# control_board.net
KiCad netlist of a schematic drawn in EAGLE
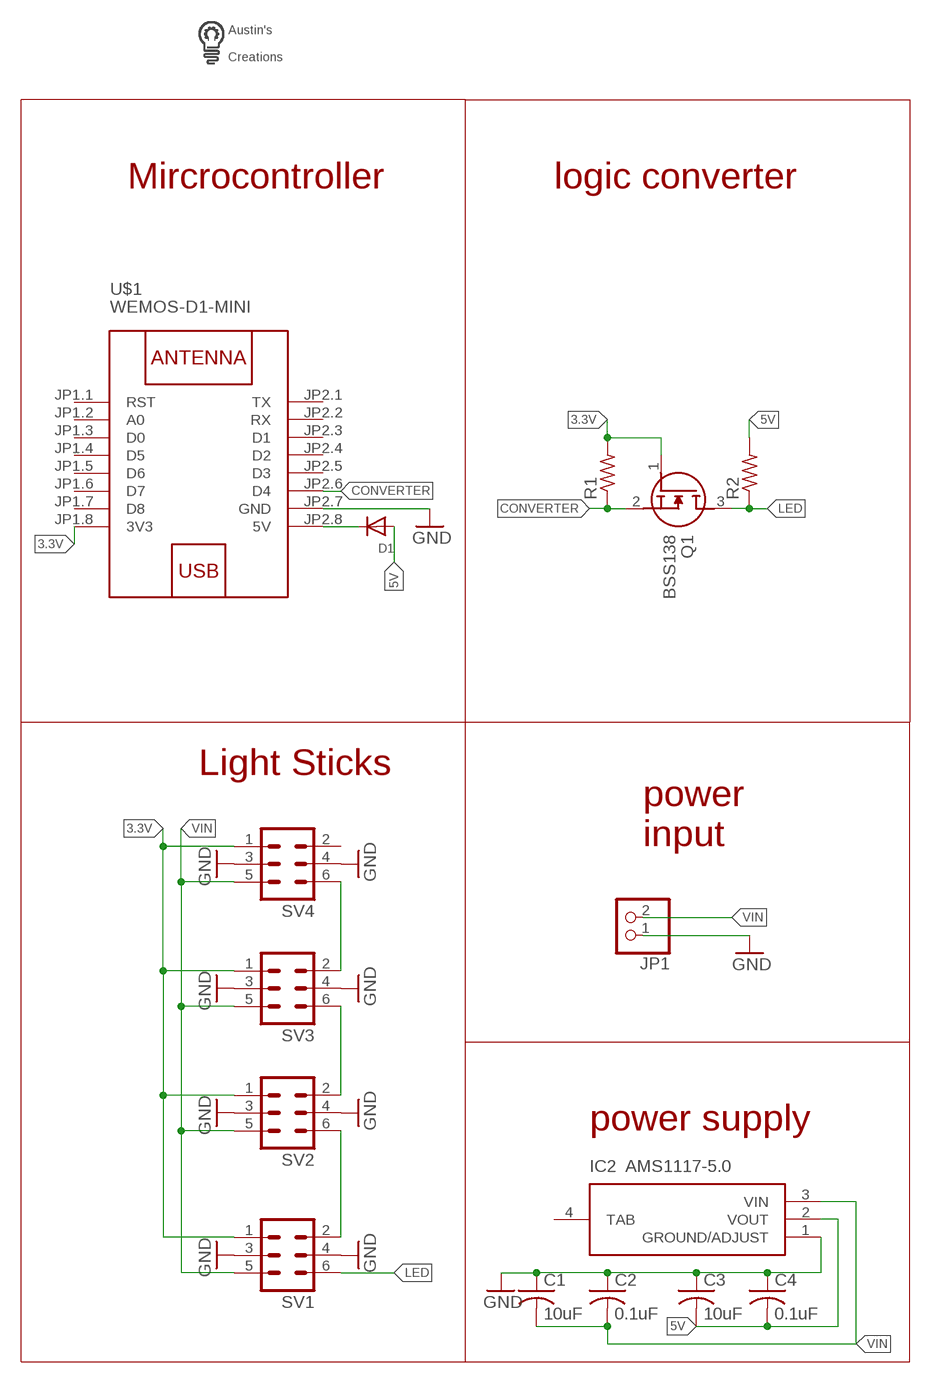
[diagram p0: schematic, sheet 1]

(export (version "E")
  (design (tool "Eeschema 10.0.6"))
  (components
    (comp (ref "C1")
      (value "10uF")
      (footprint "eagle-import:C0603")
      (libsource (lib "eagle-import") (part "C-USC0603"))
    )
    (comp (ref "C2")
      (value "0.1uF")
      (footprint "eagle-import:C0603")
      (libsource (lib "eagle-import") (part "C-USC0603"))
    )
    (comp (ref "C3")
      (value "10uF")
      (footprint "eagle-import:C0603")
      (libsource (lib "eagle-import") (part "C-USC0603"))
    )
    (comp (ref "C4")
      (value "0.1uF")
      (footprint "eagle-import:C0603")
      (libsource (lib "eagle-import") (part "C-USC0603"))
    )
    (comp (ref "D1")
      (value "DIODESOD-123")
      (footprint "eagle-import:SOD-123")
      (libsource (lib "eagle-import") (part "DIODESOD-123"))
    )
    (comp (ref "IC2")
      (value "AMS1117-5.0")
      (footprint "eagle-import:SOT229P700X180-4N")
      (libsource (lib "eagle-import") (part "AMS1117-5.0"))
    )
    (comp (ref "JP1")
      (value "PINHD-1X2")
      (footprint "eagle-import:1X02")
      (libsource (lib "eagle-import") (part "PINHD-1X2"))
    )
    (comp (ref "Q1")
      (value "BSS138")
      (footprint "eagle-import:SOT95P240X120-3N")
      (fields (field (name "MOUSER_PART_NUMBER") "512-BSS138"))
      (libsource (lib "eagle-import") (part "BSS138"))
    )
    (comp (ref "R1")
      (value "R-US_R0603")
      (footprint "eagle-import:R0603")
      (libsource (lib "eagle-import") (part "R-US_R0603"))
    )
    (comp (ref "R2")
      (value "R-US_R0603")
      (footprint "eagle-import:R0603")
      (libsource (lib "eagle-import") (part "R-US_R0603"))
    )
    (comp (ref "SV1")
      (value "MA03-2")
      (footprint "eagle-import:MA03-2")
      (libsource (lib "eagle-import") (part "MA03-2"))
    )
    (comp (ref "SV2")
      (value "MA03-2")
      (footprint "eagle-import:MA03-2")
      (libsource (lib "eagle-import") (part "MA03-2"))
    )
    (comp (ref "SV3")
      (value "MA03-2")
      (footprint "eagle-import:MA03-2")
      (libsource (lib "eagle-import") (part "MA03-2"))
    )
    (comp (ref "SV4")
      (value "MA03-2")
      (footprint "eagle-import:MA03-2")
      (libsource (lib "eagle-import") (part "MA03-2"))
    )
    (comp (ref "U$1")
      (value "WEMOS-D1-MINI")
      (footprint "eagle-import:WEMOS-D1-MINI")
      (libsource (lib "eagle-import") (part "WEMOS-D1-MINI"))
    )
    (comp (ref "U$2")
      (value "LOGO")
      (footprint "eagle-import:LOGO")
      (libsource (lib "eagle-import") (part "LOGO"))
    )
  )
  (nets
    (net (code "1") (name "3.3V") (class "Default")
      (node (ref "Q1") (pin "1") (pinfunction "G_1") (pintype "bidirectional"))
      (node (ref "R1") (pin "2") (pinfunction "2_2") (pintype "passive"))
      (node (ref "SV1") (pin "1") (pinfunction "1_1") (pintype "passive"))
      (node (ref "SV2") (pin "1") (pinfunction "1_1") (pintype "passive"))
      (node (ref "SV3") (pin "1") (pinfunction "1_1") (pintype "passive"))
      (node (ref "SV4") (pin "1") (pinfunction "1_1") (pintype "passive"))
      (node (ref "U$1") (pin "JP1.8") (pinfunction "3V3_JP1.8") (pintype "power_in"))
    )
    (net (code "2") (name "5V") (class "Default")
      (node (ref "C3") (pin "2") (pinfunction "2_2") (pintype "passive"))
      (node (ref "C4") (pin "2") (pinfunction "2_2") (pintype "passive"))
      (node (ref "D1") (pin "A") (pinfunction "A_A") (pintype "passive"))
      (node (ref "IC2") (pin "2") (pinfunction "VOUT_2") (pintype "bidirectional"))
      (node (ref "R2") (pin "2") (pinfunction "2_2") (pintype "passive"))
    )
    (net (code "3") (name "CONVERTER") (class "Default")
      (node (ref "Q1") (pin "2") (pinfunction "S_2") (pintype "bidirectional"))
      (node (ref "R1") (pin "1") (pinfunction "1_1") (pintype "passive"))
      (node (ref "U$1") (pin "JP2.6") (pinfunction "D4_JP2.6") (pintype "bidirectional"))
    )
    (net (code "4") (name "GND") (class "Default")
      (node (ref "C1") (pin "1") (pinfunction "1_1") (pintype "passive"))
      (node (ref "C2") (pin "1") (pinfunction "1_1") (pintype "passive"))
      (node (ref "C3") (pin "1") (pinfunction "1_1") (pintype "passive"))
      (node (ref "C4") (pin "1") (pinfunction "1_1") (pintype "passive"))
      (node (ref "IC2") (pin "1") (pinfunction "GROUND/ADJUST_1") (pintype "bidirectional"))
      (node (ref "JP1") (pin "1") (pinfunction "1_1") (pintype "passive"))
      (node (ref "SV1") (pin "3") (pinfunction "3_3") (pintype "passive"))
      (node (ref "SV1") (pin "4") (pinfunction "4_4") (pintype "passive"))
      (node (ref "SV2") (pin "3") (pinfunction "3_3") (pintype "passive"))
      (node (ref "SV2") (pin "4") (pinfunction "4_4") (pintype "passive"))
      (node (ref "SV3") (pin "3") (pinfunction "3_3") (pintype "passive"))
      (node (ref "SV3") (pin "4") (pinfunction "4_4") (pintype "passive"))
      (node (ref "SV4") (pin "3") (pinfunction "3_3") (pintype "passive"))
      (node (ref "SV4") (pin "4") (pinfunction "4_4") (pintype "passive"))
      (node (ref "U$1") (pin "JP2.7") (pinfunction "GND_JP2.7") (pintype "power_in"))
    )
    (net (code "5") (name "LED") (class "Default")
      (node (ref "Q1") (pin "3") (pinfunction "D_3") (pintype "bidirectional"))
      (node (ref "R2") (pin "1") (pinfunction "1_1") (pintype "passive"))
      (node (ref "SV1") (pin "6") (pinfunction "6_6") (pintype "passive"))
    )
    (net (code "6") (name "Net-(SV1-Pad2)") (class "Default")
      (node (ref "SV1") (pin "2") (pinfunction "2_2") (pintype "passive"))
      (node (ref "SV2") (pin "6") (pinfunction "6_6") (pintype "passive"))
    )
    (net (code "7") (name "Net-(SV2-Pad2)") (class "Default")
      (node (ref "SV2") (pin "2") (pinfunction "2_2") (pintype "passive"))
      (node (ref "SV3") (pin "6") (pinfunction "6_6") (pintype "passive"))
    )
    (net (code "8") (name "Net-(SV3-Pad2)") (class "Default")
      (node (ref "SV3") (pin "2") (pinfunction "2_2") (pintype "passive"))
      (node (ref "SV4") (pin "6") (pinfunction "6_6") (pintype "passive"))
    )
    (net (code "9") (name "Net-(U$1-5V)") (class "Default")
      (node (ref "D1") (pin "C") (pinfunction "C_C") (pintype "passive"))
      (node (ref "U$1") (pin "JP2.8") (pinfunction "5V_JP2.8") (pintype "power_in"))
    )
    (net (code "10") (name "VIN") (class "Default")
      (node (ref "C1") (pin "2") (pinfunction "2_2") (pintype "passive"))
      (node (ref "C2") (pin "2") (pinfunction "2_2") (pintype "passive"))
      (node (ref "IC2") (pin "3") (pinfunction "VIN_3") (pintype "bidirectional"))
      (node (ref "JP1") (pin "2") (pinfunction "2_2") (pintype "passive"))
      (node (ref "SV1") (pin "5") (pinfunction "5_5") (pintype "passive"))
      (node (ref "SV2") (pin "5") (pinfunction "5_5") (pintype "passive"))
      (node (ref "SV3") (pin "5") (pinfunction "5_5") (pintype "passive"))
      (node (ref "SV4") (pin "5") (pinfunction "5_5") (pintype "passive"))
    )
    (net (code "11") (name "unconnected-(IC2-TAB-Pad4)") (class "Default")
      (node (ref "IC2") (pin "4") (pinfunction "TAB_4") (pintype "bidirectional"))
    )
    (net (code "12") (name "unconnected-(SV4-Pad2)") (class "Default")
      (node (ref "SV4") (pin "2") (pinfunction "2_2") (pintype "passive"))
    )
    (net (code "13") (name "unconnected-(U$1-A0-PadJP1.2)") (class "Default")
      (node (ref "U$1") (pin "JP1.2") (pinfunction "A0_JP1.2") (pintype "bidirectional"))
    )
    (net (code "14") (name "unconnected-(U$1-D0-PadJP1.3)") (class "Default")
      (node (ref "U$1") (pin "JP1.3") (pinfunction "D0_JP1.3") (pintype "bidirectional"))
    )
    (net (code "15") (name "unconnected-(U$1-D1-PadJP2.3)") (class "Default")
      (node (ref "U$1") (pin "JP2.3") (pinfunction "D1_JP2.3") (pintype "bidirectional"))
    )
    (net (code "16") (name "unconnected-(U$1-D2-PadJP2.4)") (class "Default")
      (node (ref "U$1") (pin "JP2.4") (pinfunction "D2_JP2.4") (pintype "bidirectional"))
    )
    (net (code "17") (name "unconnected-(U$1-D3-PadJP2.5)") (class "Default")
      (node (ref "U$1") (pin "JP2.5") (pinfunction "D3_JP2.5") (pintype "bidirectional"))
    )
    (net (code "18") (name "unconnected-(U$1-D5-PadJP1.4)") (class "Default")
      (node (ref "U$1") (pin "JP1.4") (pinfunction "D5_JP1.4") (pintype "bidirectional"))
    )
    (net (code "19") (name "unconnected-(U$1-D6-PadJP1.5)") (class "Default")
      (node (ref "U$1") (pin "JP1.5") (pinfunction "D6_JP1.5") (pintype "bidirectional"))
    )
    (net (code "20") (name "unconnected-(U$1-D7-PadJP1.6)") (class "Default")
      (node (ref "U$1") (pin "JP1.6") (pinfunction "D7_JP1.6") (pintype "bidirectional"))
    )
    (net (code "21") (name "unconnected-(U$1-D8-PadJP1.7)") (class "Default")
      (node (ref "U$1") (pin "JP1.7") (pinfunction "D8_JP1.7") (pintype "bidirectional"))
    )
    (net (code "22") (name "unconnected-(U$1-RST-PadJP1.1)") (class "Default")
      (node (ref "U$1") (pin "JP1.1") (pinfunction "RST_JP1.1") (pintype "bidirectional"))
    )
    (net (code "23") (name "unconnected-(U$1-RX-PadJP2.2)") (class "Default")
      (node (ref "U$1") (pin "JP2.2") (pinfunction "RX_JP2.2") (pintype "bidirectional"))
    )
    (net (code "24") (name "unconnected-(U$1-TX-PadJP2.1)") (class "Default")
      (node (ref "U$1") (pin "JP2.1") (pinfunction "TX_JP2.1") (pintype "bidirectional"))
    )
  )
)
